# projeto.net
KiCad netlist of a schematic drawn in EAGLE
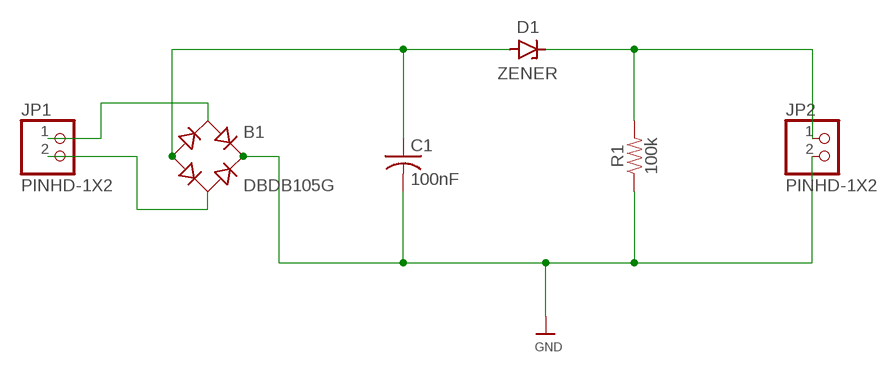
[diagram p0: schematic, sheet 1]

(export (version "E")
  (design (tool "Eeschema 10.0.6"))
  (components
    (comp (ref "B1")
      (value "DBDB105G")
      (footprint "eagle-import:DB")
      (libsource (lib "eagle-import") (part "DB?GDB105"))
    )
    (comp (ref "C1")
      (value "100nF")
      (footprint "eagle-import:C025-025X050")
      (libsource (lib "eagle-import") (part "C-US025-025X050"))
    )
    (comp (ref "D1")
      (value "ZENER")
      (footprint "eagle-import:DIOM5336X265N")
      (libsource (lib "eagle-import") (part "ZENERDO-214AA(SMB)"))
    )
    (comp (ref "JP1")
      (value "PINHD-1X2")
      (footprint "eagle-import:1X02")
      (libsource (lib "eagle-import") (part "PINHD-1X2"))
    )
    (comp (ref "JP2")
      (value "PINHD-1X2")
      (footprint "eagle-import:1X02")
      (libsource (lib "eagle-import") (part "PINHD-1X2"))
    )
    (comp (ref "R1")
      (value "100k")
      (footprint "eagle-import:1210")
      (libsource (lib "eagle-import") (part "0.1OHM-1210-1/2W-1%"))
    )
  )
  (nets
    (net (code "1") (name "GND") (class "Default")
      (node (ref "B1") (pin "+") (pinfunction "+_+") (pintype "passive"))
      (node (ref "C1") (pin "2") (pinfunction "2_2") (pintype "passive"))
      (node (ref "JP2") (pin "2") (pinfunction "2_2") (pintype "passive"))
      (node (ref "R1") (pin "1") (pinfunction "1_1") (pintype "passive"))
    )
    (net (code "2") (name "Net-(B1-PadAC1)") (class "Default")
      (node (ref "B1") (pin "AC1") (pinfunction "AC1_AC1") (pintype "passive"))
      (node (ref "JP1") (pin "1") (pinfunction "1_1") (pintype "passive"))
    )
    (net (code "3") (name "Net-(B1-PadAC2)") (class "Default")
      (node (ref "B1") (pin "AC2") (pinfunction "AC2_AC2") (pintype "passive"))
      (node (ref "JP1") (pin "2") (pinfunction "2_2") (pintype "passive"))
    )
    (net (code "4") (name "Net-(D1-A)") (class "Default")
      (node (ref "B1") (pin "-") (pinfunction "-_-") (pintype "passive"))
      (node (ref "C1") (pin "1") (pinfunction "1_1") (pintype "passive"))
      (node (ref "D1") (pin "2") (pinfunction "A_2") (pintype "passive"))
    )
    (net (code "5") (name "Net-(D1-C)") (class "Default")
      (node (ref "D1") (pin "1") (pinfunction "C_1") (pintype "passive"))
      (node (ref "JP2") (pin "1") (pinfunction "1_1") (pintype "passive"))
      (node (ref "R1") (pin "2") (pinfunction "2_2") (pintype "passive"))
    )
  )
)
